# Sheet_Power.net
KiCad netlist of a schematic drawn in Altium Designer
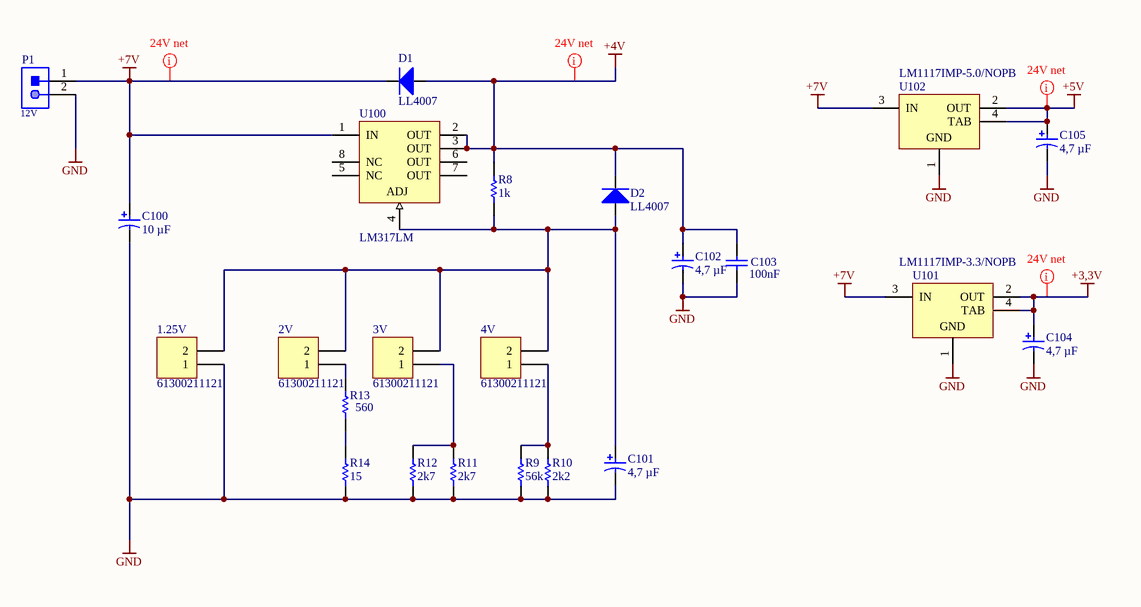
[diagram p0: Sheet_Power.SchDoc]

(export (version "E")
  (design (tool "Eeschema 10.0.6"))
  (components
    (comp (ref "1.25V")
      (value "61300211121")
      (footprint "61300211121")
      (description "2Pol; gerade; WR-PHD 2.54 mm THT Pin Header")
      (fields (field (name "MANUFACTURER") "Wurth Electronics"))
      (libsource (lib "Altium Vault EMBL 3") (part "CMP-001-0071-1"))
    )
    (comp (ref "2V")
      (value "61300211121")
      (footprint "61300211121")
      (description "2Pol; gerade; WR-PHD 2.54 mm THT Pin Header")
      (fields (field (name "MANUFACTURER") "Wurth Electronics"))
      (libsource (lib "Altium Vault EMBL 3") (part "CMP-001-0071-1"))
    )
    (comp (ref "3V")
      (value "61300211121")
      (footprint "61300211121")
      (description "2Pol; gerade; WR-PHD 2.54 mm THT Pin Header")
      (fields (field (name "MANUFACTURER") "Wurth Electronics"))
      (libsource (lib "Altium Vault EMBL 3") (part "CMP-001-0071-1"))
    )
    (comp (ref "4V")
      (value "61300211121")
      (footprint "61300211121")
      (description "2Pol; gerade; WR-PHD 2.54 mm THT Pin Header")
      (fields (field (name "MANUFACTURER") "Wurth Electronics"))
      (libsource (lib "Altium Vault EMBL 3") (part "CMP-001-0071-1"))
    )
    (comp (ref "C100")
      (value "10 µF")
      (footprint "KEMT-520-D_Low")
      (description "10 µF, 35V, 125 mOhm, Gr. D\npartnumb: T495D106K035ATE125")
      (fields (field (name "MANUFACTURER") "KEMET") (field (name "TOLERANCE") "±10%"))
      (libsource (lib "Altium Vault EMBL") (part "CMP-001-0033-3"))
    )
    (comp (ref "C101")
      (value "4,7 µF")
      (footprint "A Package")
      (description "4,7 µF; 6V; Gr. A; T491A475K006AT")
      (fields (field (name "MANUFACTURER") "KEMET") (field (name "TOLERANCE") "±10%"))
      (libsource (lib "Altium Vault EMBL") (part "CMP-001-0039-3"))
    )
    (comp (ref "C102")
      (value "4,7 µF")
      (footprint "A Package")
      (description "4,7 µF; 6V; Gr. A; T491A475K006AT")
      (fields (field (name "MANUFACTURER") "KEMET") (field (name "TOLERANCE") "±10%"))
      (libsource (lib "Altium Vault EMBL") (part "CMP-001-0039-3"))
    )
    (comp (ref "C103")
      (value "100nF")
      (footprint "CAPC2013X88X50ML20T25")
      (description "generic 0805 COG oder X7R Vielschichtkondensatoren max. +/-10%")
      (libsource (lib "Altium Vault EMBL 3") (part "CMP-001-0082-2"))
    )
    (comp (ref "C104")
      (value "4,7 µF")
      (footprint "A Package")
      (description "4,7 µF; 6V; Gr. A; T491A475K006AT")
      (fields (field (name "MANUFACTURER") "KEMET") (field (name "TOLERANCE") "±10%"))
      (libsource (lib "Altium Vault EMBL") (part "CMP-001-0039-3"))
    )
    (comp (ref "C105")
      (value "4,7 µF")
      (footprint "A Package")
      (description "4,7 µF; 6V; Gr. A; T491A475K006AT")
      (fields (field (name "MANUFACTURER") "KEMET") (field (name "TOLERANCE") "±10%"))
      (libsource (lib "Altium Vault EMBL") (part "CMP-001-0039-3"))
    )
    (comp (ref "D1")
      (value "LL4007")
      (footprint "LL4007")
      (description "LL4007;  Vf 1,1V @ 1A, If = 1A")
      (fields (field (name "MANUFACTURER") "TAIWAN SEMICONDUCTOR") (field (name "PARTNUMBER") "LL4007G L2"))
      (libsource (lib "Altium Vault EMBL") (part "CMP-001-0049-2"))
    )
    (comp (ref "D2")
      (value "LL4007")
      (footprint "LL4007")
      (description "LL4007;  Vf 1,1V @ 1A, If = 1A")
      (fields (field (name "MANUFACTURER") "TAIWAN SEMICONDUCTOR") (field (name "PARTNUMBER") "LL4007G L2"))
      (libsource (lib "Altium Vault EMBL") (part "CMP-001-0049-2"))
    )
    (comp (ref "P1")
      (value "12V")
      (footprint "66100211622")
      (description "WR-WTB 2.54 mm Male Vertical Shrouded Header 2 Pins")
      (fields (field (name "PARTNUMBER") "66100211622") (field (name "MANUFACTURER") "Wurth Electronics"))
      (libsource (lib "EMBL") (part "WE-CN-1P-M-R2"))
    )
    (comp (ref "R8")
      (value "1k")
      (footprint "YAGO-RC0805_M")
      (description "0805 Yageo Standard BlackBox Resistors")
      (fields (field (name "TOLERANCE") "±1%") (field (name "MANUFACTURER") "Yageo"))
      (libsource (lib "Altium Vault EMBL") (part "0805"))
    )
    (comp (ref "R9")
      (value "56k")
      (footprint "YAGO-RC0805_M")
      (description "0805 Yageo Standard BlackBox Resistors")
      (fields (field (name "TOLERANCE") "±1%") (field (name "MANUFACTURER") "Yageo"))
      (libsource (lib "Altium Vault EMBL") (part "CMP-001-0027-2"))
    )
    (comp (ref "R10")
      (value "2k2")
      (footprint "YAGO-RC0805_M")
      (description "0805 Yageo Standard BlackBox Resistors")
      (fields (field (name "TOLERANCE") "±1%") (field (name "MANUFACTURER") "Yageo"))
      (libsource (lib "Altium Vault EMBL") (part "CMP-001-0027-2"))
    )
    (comp (ref "R11")
      (value "2k7")
      (footprint "YAGO-RC0805_M")
      (description "0805 Yageo Standard BlackBox Resistors")
      (fields (field (name "TOLERANCE") "±1%") (field (name "MANUFACTURER") "Yageo"))
      (libsource (lib "Altium Vault EMBL") (part "CMP-001-0027-2"))
    )
    (comp (ref "R12")
      (value "2k7")
      (footprint "YAGO-RC0805_M")
      (description "0805 Yageo Standard BlackBox Resistors")
      (fields (field (name "TOLERANCE") "±1%") (field (name "MANUFACTURER") "Yageo"))
      (libsource (lib "Altium Vault EMBL") (part "CMP-001-0027-2"))
    )
    (comp (ref "R13")
      (value "560")
      (footprint "YAGO-RC0805_M")
      (description "0805 Yageo Standard BlackBox Resistors")
      (fields (field (name "TOLERANCE") "±1%") (field (name "MANUFACTURER") "Yageo"))
      (libsource (lib "Altium Vault EMBL") (part "CMP-001-0027-2"))
    )
    (comp (ref "R14")
      (value "15")
      (footprint "YAGO-RC0805_M")
      (description "0805 Yageo Standard BlackBox Resistors")
      (fields (field (name "TOLERANCE") "±1%") (field (name "MANUFACTURER") "Yageo"))
      (libsource (lib "Altium Vault EMBL") (part "CMP-001-0027-2"))
    )
    (comp (ref "U100")
      (value "LM317LM")
      (footprint "M08A_M")
      (description "LM317LM/NOPB; 8PIN SOIC; 0,1A")
      (fields (field (name "PARTNUMBER") "LM317LM/NOPB") (field (name "MANUFACTURER") "Texas Instruments"))
      (libsource (lib "Altium Vault EMBL") (part "CMP-001-0042-1"))
    )
    (comp (ref "U101")
      (value "LM1117IMP-3.3/NOPB")
      (footprint "DCY0004A_N")
      (description "800mA Low-Dropout Linear Regulator, 4-pin SOT-223, Pb-Free")
      (fields (field (name "MANUFACTURER") "Texas Instruments"))
      (libsource (lib "Altium Vault EMBL") (part "CMP-00484-1"))
    )
    (comp (ref "U102")
      (value "LM1117IMP-5.0/NOPB")
      (footprint "DCY0004A_M")
      (description "800mA Low-Dropout Linear Regulator, 4-pin SOT-223, Pb-Free")
      (fields (field (name "MANUFACTURER") "Texas Instruments"))
      (libsource (lib "Altium Vault EMBL") (part "CMP-00485-1"))
    )
  )
  (nets
    (net (code "1") (name "+3,3V") (class "Default")
      (node (ref "C104") (pin "1") (pinfunction "1_1") (pintype "passive"))
      (node (ref "U101") (pin "2") (pinfunction "OUT_2") (pintype "power_in"))
      (node (ref "U101") (pin "4") (pinfunction "TAB_4") (pintype "power_in"))
    )
    (net (code "2") (name "+4V") (class "Default")
      (node (ref "C102") (pin "1") (pinfunction "1_1") (pintype "passive"))
      (node (ref "C103") (pin "2") (pinfunction "2_2") (pintype "passive"))
      (node (ref "D1") (pin "1") (pinfunction "A_1") (pintype "passive"))
      (node (ref "D2") (pin "2") (pinfunction "K_2") (pintype "passive"))
      (node (ref "R8") (pin "2") (pinfunction "2_2") (pintype "passive"))
      (node (ref "U100") (pin "2") (pinfunction "OUT_2") (pintype "power_in"))
      (node (ref "U100") (pin "3") (pinfunction "OUT_3") (pintype "power_in"))
    )
    (net (code "3") (name "+5V") (class "Default")
      (node (ref "C105") (pin "1") (pinfunction "1_1") (pintype "passive"))
      (node (ref "U102") (pin "2") (pinfunction "OUT_2") (pintype "power_in"))
      (node (ref "U102") (pin "4") (pinfunction "TAB_4") (pintype "power_in"))
    )
    (net (code "4") (name "+7V") (class "Default")
      (node (ref "C100") (pin "1") (pinfunction "1_1") (pintype "passive"))
      (node (ref "D1") (pin "2") (pinfunction "K_2") (pintype "passive"))
      (node (ref "P1") (pin "1") (pinfunction "1_1") (pintype "passive"))
      (node (ref "U100") (pin "1") (pinfunction "IN_1") (pintype "power_in"))
      (node (ref "U101") (pin "3") (pinfunction "IN_3") (pintype "power_in"))
      (node (ref "U102") (pin "3") (pinfunction "IN_3") (pintype "power_in"))
    )
    (net (code "5") (name "GND") (class "Default")
      (node (ref "1.25V") (pin "1") (pinfunction "1_1") (pintype "passive"))
      (node (ref "C100") (pin "2") (pinfunction "2_2") (pintype "passive"))
      (node (ref "C101") (pin "2") (pinfunction "2_2") (pintype "passive"))
      (node (ref "C102") (pin "2") (pinfunction "2_2") (pintype "passive"))
      (node (ref "C103") (pin "1") (pinfunction "1_1") (pintype "passive"))
      (node (ref "C104") (pin "2") (pinfunction "2_2") (pintype "passive"))
      (node (ref "C105") (pin "2") (pinfunction "2_2") (pintype "passive"))
      (node (ref "P1") (pin "2") (pinfunction "2_2") (pintype "passive"))
      (node (ref "R10") (pin "1") (pinfunction "1_1") (pintype "passive"))
      (node (ref "R11") (pin "1") (pinfunction "1_1") (pintype "passive"))
      (node (ref "R12") (pin "1") (pinfunction "1_1") (pintype "passive"))
      (node (ref "R14") (pin "1") (pinfunction "1_1") (pintype "passive"))
      (node (ref "R9") (pin "1") (pinfunction "1_1") (pintype "passive"))
      (node (ref "U101") (pin "1") (pinfunction "GND_1") (pintype "power_in"))
      (node (ref "U102") (pin "1") (pinfunction "GND_1") (pintype "power_in"))
    )
    (net (code "6") (name "Net-(2V-Pad1)") (class "Default")
      (node (ref "2V") (pin "1") (pinfunction "1_1") (pintype "passive"))
      (node (ref "R13") (pin "2") (pinfunction "2_2") (pintype "passive"))
    )
    (net (code "7") (name "Net-(3V-Pad1)") (class "Default")
      (node (ref "3V") (pin "1") (pinfunction "1_1") (pintype "passive"))
      (node (ref "R11") (pin "2") (pinfunction "2_2") (pintype "passive"))
      (node (ref "R12") (pin "2") (pinfunction "2_2") (pintype "passive"))
    )
    (net (code "8") (name "Net-(4V-Pad1)") (class "Default")
      (node (ref "4V") (pin "1") (pinfunction "1_1") (pintype "passive"))
      (node (ref "R10") (pin "2") (pinfunction "2_2") (pintype "passive"))
      (node (ref "R9") (pin "2") (pinfunction "2_2") (pintype "passive"))
    )
    (net (code "9") (name "Net-(D2-A)") (class "Default")
      (node (ref "1.25V") (pin "2") (pinfunction "2_2") (pintype "passive"))
      (node (ref "2V") (pin "2") (pinfunction "2_2") (pintype "passive"))
      (node (ref "3V") (pin "2") (pinfunction "2_2") (pintype "passive"))
      (node (ref "4V") (pin "2") (pinfunction "2_2") (pintype "passive"))
      (node (ref "C101") (pin "1") (pinfunction "1_1") (pintype "passive"))
      (node (ref "D2") (pin "1") (pinfunction "A_1") (pintype "passive"))
      (node (ref "R8") (pin "1") (pinfunction "1_1") (pintype "passive"))
      (node (ref "U100") (pin "4") (pinfunction "ADJ_4") (pintype "input"))
    )
    (net (code "10") (name "Net-(R13-Pad1)") (class "Default")
      (node (ref "R13") (pin "1") (pinfunction "1_1") (pintype "passive"))
      (node (ref "R14") (pin "2") (pinfunction "2_2") (pintype "passive"))
    )
    (net (code "11") (name "unconnected-(U100-NC-Pad5)") (class "Default")
      (node (ref "U100") (pin "5") (pinfunction "NC_5") (pintype "passive"))
    )
    (net (code "12") (name "unconnected-(U100-NC-Pad8)") (class "Default")
      (node (ref "U100") (pin "8") (pinfunction "NC_8") (pintype "passive"))
    )
    (net (code "13") (name "unconnected-(U100-OUT-Pad6)") (class "Default")
      (node (ref "U100") (pin "6") (pinfunction "OUT_6") (pintype "power_in"))
    )
    (net (code "14") (name "unconnected-(U100-OUT-Pad7)") (class "Default")
      (node (ref "U100") (pin "7") (pinfunction "OUT_7") (pintype "power_in"))
    )
  )
)
